# musicbox_mechanical-02.net
KiCad netlist of a schematic drawn in EAGLE
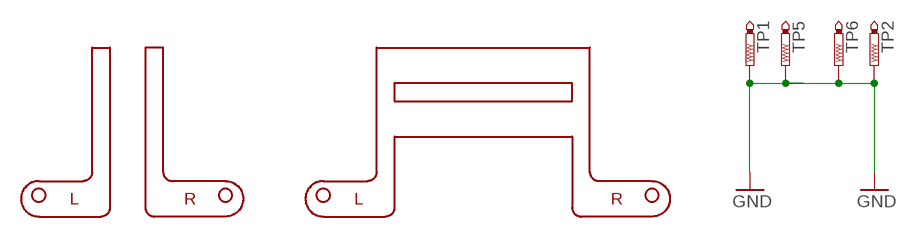
[diagram p0: schematic, sheet 1]

(export (version "E")
  (design (tool "Eeschema 10.0.6"))
  (components
    (comp (ref "TP1")
      (value "PTR1B1,27")
      (footprint "eagle-import:B1,27")
      (libsource (lib "eagle-import") (part "PTR1B1,27"))
    )
    (comp (ref "TP2")
      (value "PTR1B1,27")
      (footprint "eagle-import:B1,27")
      (libsource (lib "eagle-import") (part "PTR1B1,27"))
    )
    (comp (ref "TP5")
      (value "PTR1B1,27")
      (footprint "eagle-import:B1,27")
      (libsource (lib "eagle-import") (part "PTR1B1,27"))
    )
    (comp (ref "TP6")
      (value "PTR1B1,27")
      (footprint "eagle-import:B1,27")
      (libsource (lib "eagle-import") (part "PTR1B1,27"))
    )
    (comp (ref "U$1")
      (value "LEFT-FOOT")
      (footprint "eagle-import:LEFT-FOOT")
      (libsource (lib "eagle-import") (part "LEFT-FOOT"))
    )
    (comp (ref "U$3")
      (value "RIGHT-FOOT")
      (footprint "eagle-import:RIGHT-FOOT")
      (libsource (lib "eagle-import") (part "RIGHT-FOOT"))
    )
    (comp (ref "U$5")
      (value "TOP-PART")
      (footprint "eagle-import:TOP-PART")
      (libsource (lib "eagle-import") (part "TOP-PART"))
    )
  )
  (nets
    (net (code "1") (name "GND") (class "Default")
      (node (ref "TP1") (pin "TP") (pinfunction "TP_TP") (pintype "input"))
      (node (ref "TP2") (pin "TP") (pinfunction "TP_TP") (pintype "input"))
      (node (ref "TP5") (pin "TP") (pinfunction "TP_TP") (pintype "input"))
      (node (ref "TP6") (pin "TP") (pinfunction "TP_TP") (pintype "input"))
    )
  )
)
